# mainv4.net
KiCad netlist of a schematic drawn in EAGLE
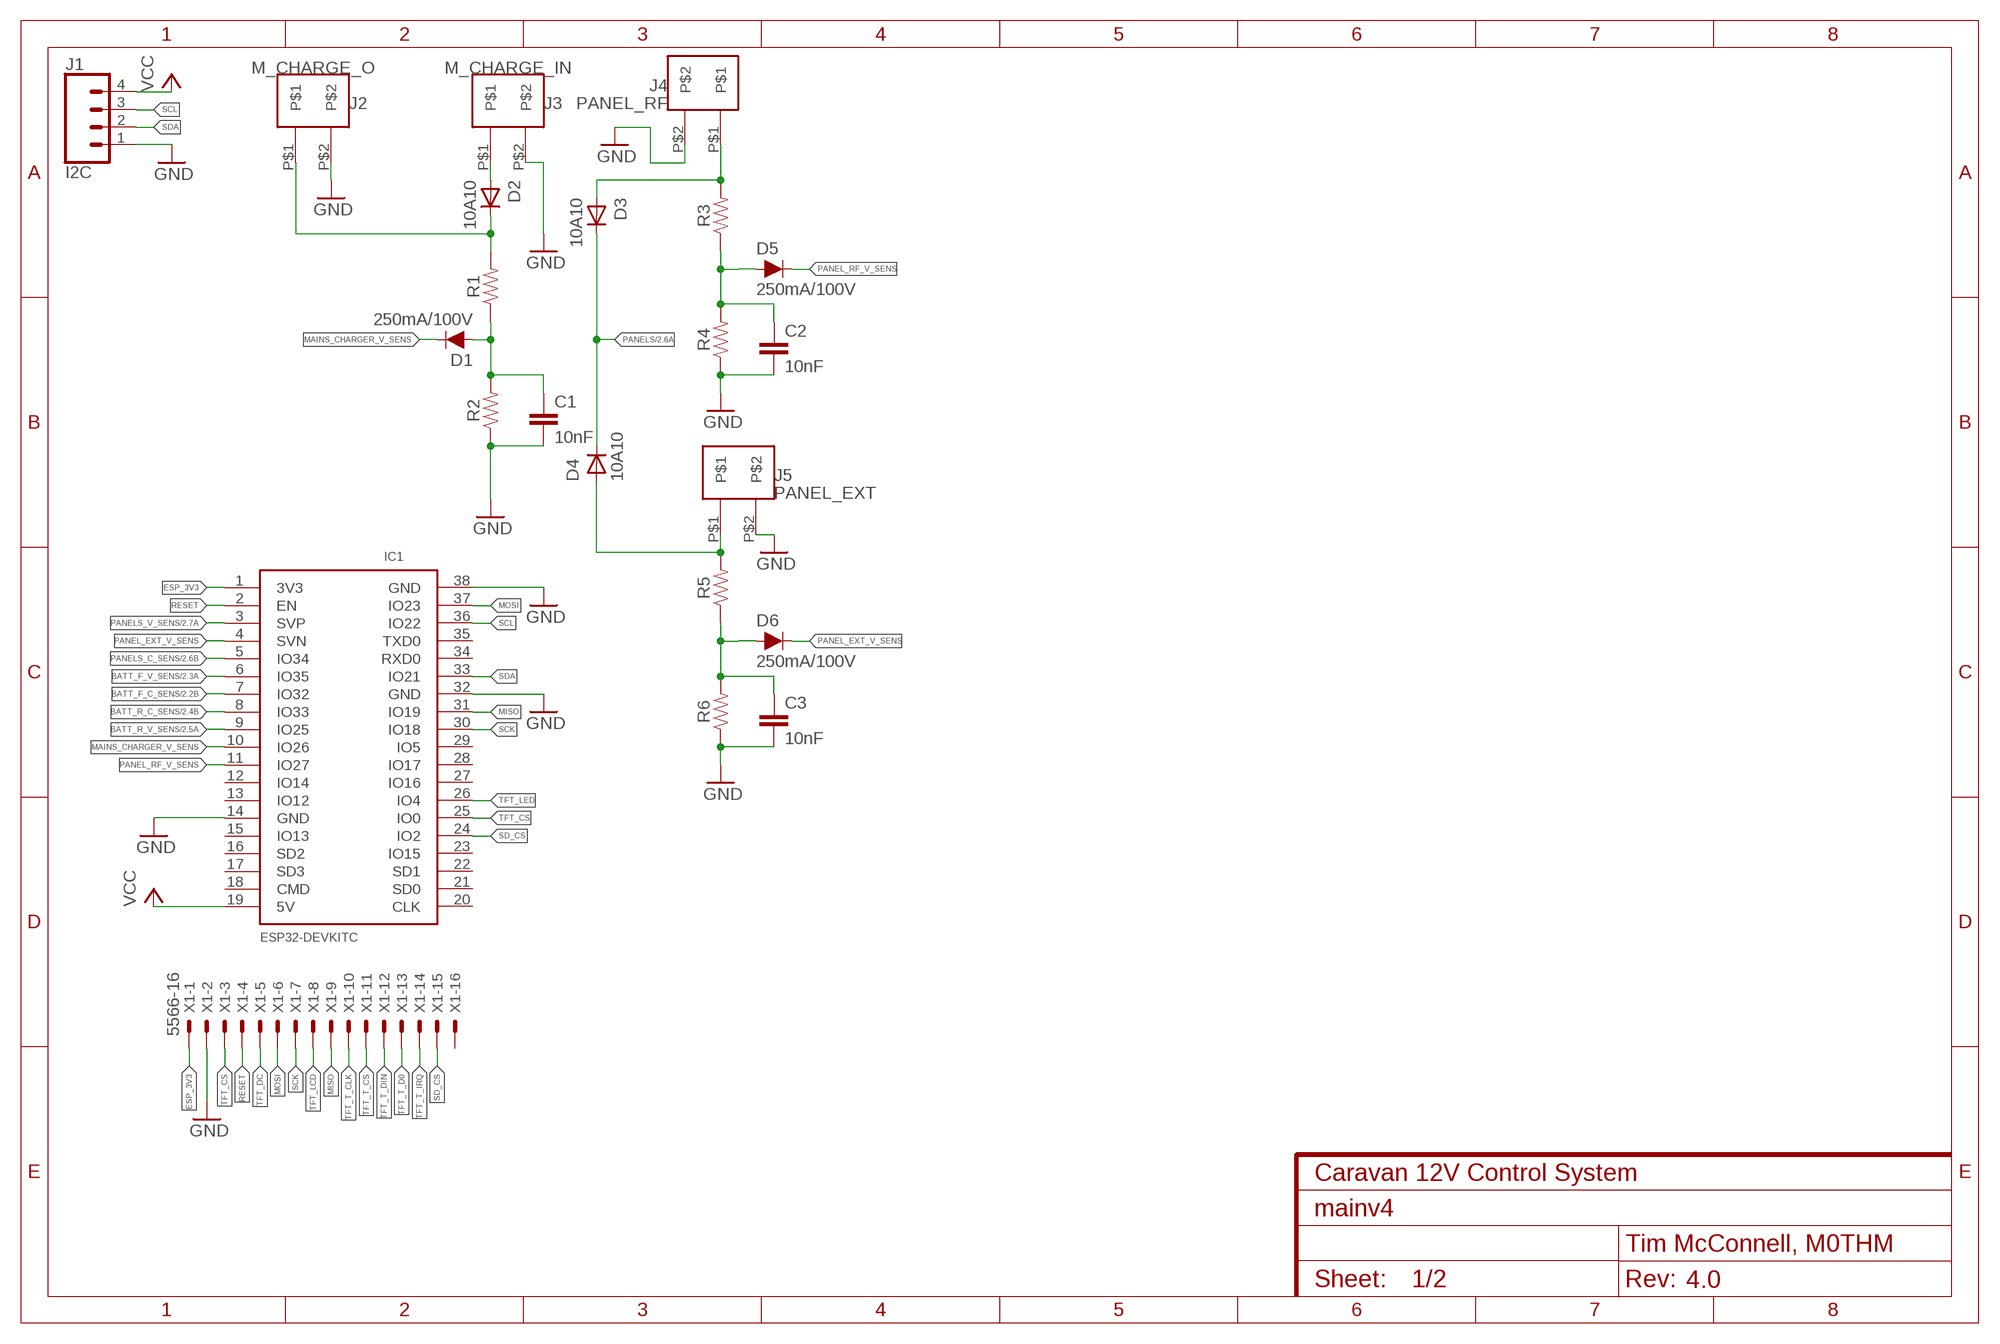
[diagram p0: schematic, sheet 1]
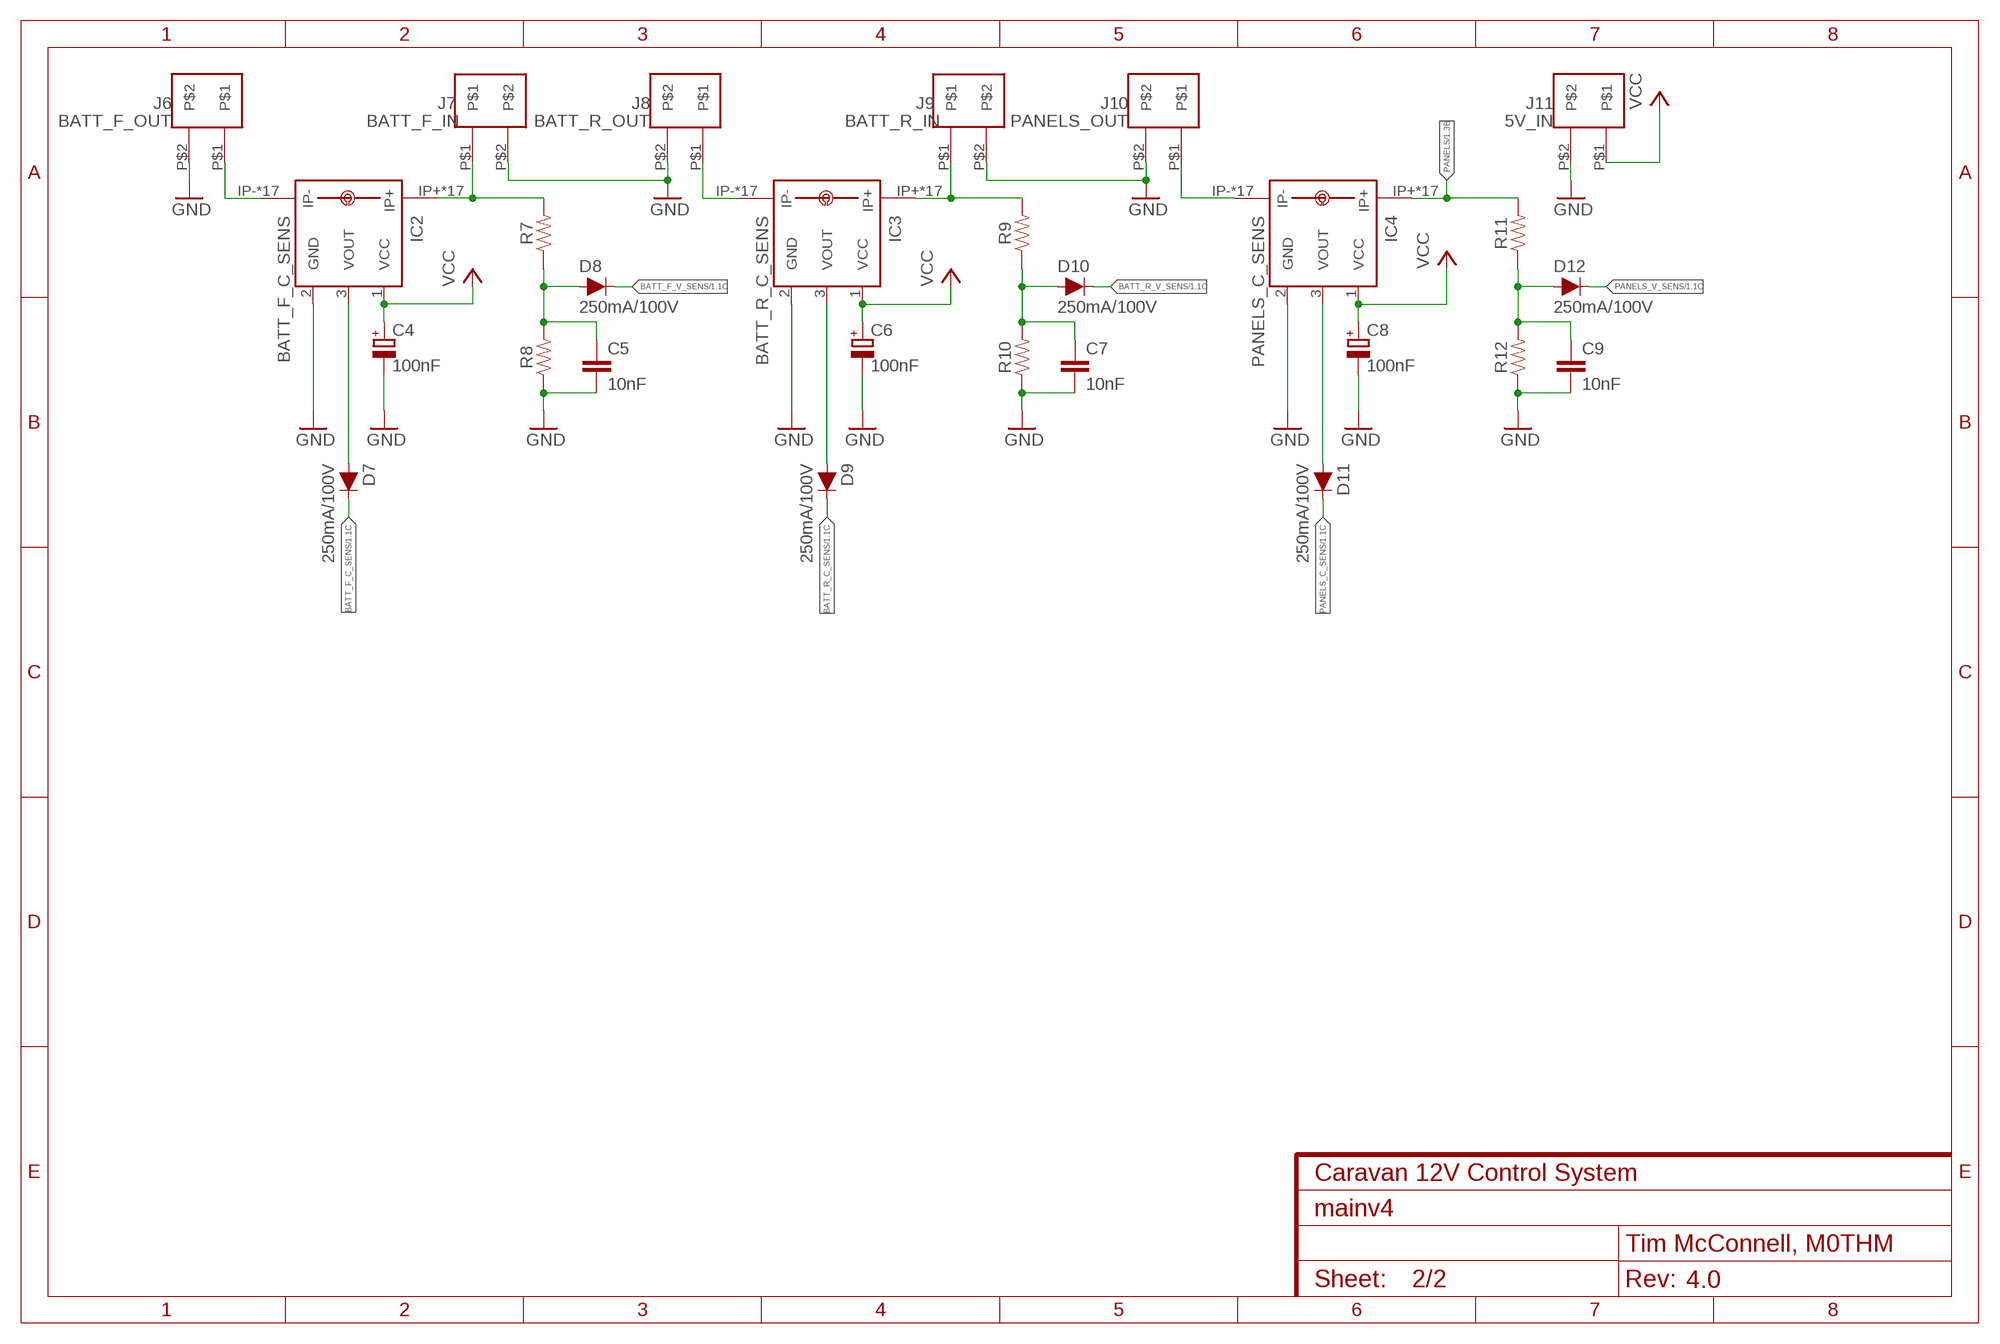
[diagram p1: schematic, sheet 2]

(export (version "E")
  (design (tool "Eeschema 10.0.6"))
  (components
    (comp (ref "C4")
      (value "100nF")
      (footprint "eagle-import:PANASONIC_E")
      (libsource (lib "eagle-import") (part "CPOL-EUE"))
    )
    (comp (ref "C5")
      (value "10nF")
      (footprint "eagle-import:0603")
      (libsource (lib "eagle-import") (part "10NF-0603-50V-10%"))
    )
    (comp (ref "C6")
      (value "100nF")
      (footprint "eagle-import:PANASONIC_E")
      (libsource (lib "eagle-import") (part "CPOL-EUE"))
    )
    (comp (ref "C7")
      (value "10nF")
      (footprint "eagle-import:0603")
      (libsource (lib "eagle-import") (part "10NF-0603-50V-10%"))
    )
    (comp (ref "C8")
      (value "100nF")
      (footprint "eagle-import:PANASONIC_E")
      (libsource (lib "eagle-import") (part "CPOL-EUE"))
    )
    (comp (ref "C9")
      (value "10nF")
      (footprint "eagle-import:0603")
      (libsource (lib "eagle-import") (part "10NF-0603-50V-10%"))
    )
    (comp (ref "D7")
      (value "250mA/100V")
      (footprint "eagle-import:SOD-323")
      (libsource (lib "eagle-import") (part "DIODE-BAS16J"))
    )
    (comp (ref "D8")
      (value "250mA/100V")
      (footprint "eagle-import:SOD-323")
      (libsource (lib "eagle-import") (part "DIODE-BAS16J"))
    )
    (comp (ref "D9")
      (value "250mA/100V")
      (footprint "eagle-import:SOD-323")
      (libsource (lib "eagle-import") (part "DIODE-BAS16J"))
    )
    (comp (ref "D10")
      (value "250mA/100V")
      (footprint "eagle-import:SOD-323")
      (libsource (lib "eagle-import") (part "DIODE-BAS16J"))
    )
    (comp (ref "D11")
      (value "250mA/100V")
      (footprint "eagle-import:SOD-323")
      (libsource (lib "eagle-import") (part "DIODE-BAS16J"))
    )
    (comp (ref "D12")
      (value "250mA/100V")
      (footprint "eagle-import:SOD-323")
      (libsource (lib "eagle-import") (part "DIODE-BAS16J"))
    )
    (comp (ref "IC2")
      (value "BATT_F_C_SENS")
      (footprint "eagle-import:CB-PFF")
      (fields (field (name "MPN") "ACS758ECB-200B-PFF-T"))
      (libsource (lib "eagle-import") (part "ACS758ECB-200B-PFF-T"))
    )
    (comp (ref "IC3")
      (value "BATT_R_C_SENS")
      (footprint "eagle-import:CB-PFF")
      (fields (field (name "MPN") "ACS758ECB-200B-PFF-T"))
      (libsource (lib "eagle-import") (part "ACS758ECB-200B-PFF-T"))
    )
    (comp (ref "IC4")
      (value "PANELS_C_SENS")
      (footprint "eagle-import:CB-PFF")
      (fields (field (name "MPN") "ACS758ECB-200B-PFF-T"))
      (libsource (lib "eagle-import") (part "ACS758ECB-200B-PFF-T"))
    )
    (comp (ref "J6")
      (value "BATT_F_OUT")
      (footprint "eagle-import:40A-2PIN")
      (libsource (lib "eagle-import") (part "40A-2PIN"))
    )
    (comp (ref "J7")
      (value "BATT_F_IN")
      (footprint "eagle-import:40A-2PIN")
      (libsource (lib "eagle-import") (part "40A-2PIN"))
    )
    (comp (ref "J8")
      (value "BATT_R_OUT")
      (footprint "eagle-import:40A-2PIN")
      (libsource (lib "eagle-import") (part "40A-2PIN"))
    )
    (comp (ref "J9")
      (value "BATT_R_IN")
      (footprint "eagle-import:40A-2PIN")
      (libsource (lib "eagle-import") (part "40A-2PIN"))
    )
    (comp (ref "J10")
      (value "PANELS_OUT")
      (footprint "eagle-import:40A-2PIN")
      (libsource (lib "eagle-import") (part "40A-2PIN"))
    )
    (comp (ref "J11")
      (value "5V_IN")
      (footprint "eagle-import:40A-2PIN")
      (libsource (lib "eagle-import") (part "40A-2PIN"))
    )
    (comp (ref "R7")
      (value "RESISTOR0805")
      (footprint "eagle-import:0805")
      (libsource (lib "eagle-import") (part "RESISTOR0805"))
    )
    (comp (ref "R8")
      (value "RESISTOR0805")
      (footprint "eagle-import:0805")
      (libsource (lib "eagle-import") (part "RESISTOR0805"))
    )
    (comp (ref "R9")
      (value "RESISTOR0805")
      (footprint "eagle-import:0805")
      (libsource (lib "eagle-import") (part "RESISTOR0805"))
    )
    (comp (ref "R10")
      (value "RESISTOR0805")
      (footprint "eagle-import:0805")
      (libsource (lib "eagle-import") (part "RESISTOR0805"))
    )
    (comp (ref "R11")
      (value "RESISTOR0805")
      (footprint "eagle-import:0805")
      (libsource (lib "eagle-import") (part "RESISTOR0805"))
    )
    (comp (ref "R12")
      (value "RESISTOR0805")
      (footprint "eagle-import:0805")
      (libsource (lib "eagle-import") (part "RESISTOR0805"))
    )
    (comp (ref "C1")
      (value "10nF")
      (footprint "eagle-import:0603")
      (libsource (lib "eagle-import") (part "10NF-0603-50V-10%"))
    )
    (comp (ref "C2")
      (value "10nF")
      (footprint "eagle-import:0603")
      (libsource (lib "eagle-import") (part "10NF-0603-50V-10%"))
    )
    (comp (ref "C3")
      (value "10nF")
      (footprint "eagle-import:0603")
      (libsource (lib "eagle-import") (part "10NF-0603-50V-10%"))
    )
    (comp (ref "D1")
      (value "250mA/100V")
      (footprint "eagle-import:SOD-323")
      (libsource (lib "eagle-import") (part "DIODE-BAS16J"))
    )
    (comp (ref "D2")
      (value "10A10")
      (footprint "eagle-import:AG")
      (libsource (lib "eagle-import") (part "10A10"))
    )
    (comp (ref "D3")
      (value "10A10")
      (footprint "eagle-import:AG")
      (libsource (lib "eagle-import") (part "10A10"))
    )
    (comp (ref "D4")
      (value "10A10")
      (footprint "eagle-import:AG")
      (libsource (lib "eagle-import") (part "10A10"))
    )
    (comp (ref "D5")
      (value "250mA/100V")
      (footprint "eagle-import:SOD-323")
      (libsource (lib "eagle-import") (part "DIODE-BAS16J"))
    )
    (comp (ref "D6")
      (value "250mA/100V")
      (footprint "eagle-import:SOD-323")
      (libsource (lib "eagle-import") (part "DIODE-BAS16J"))
    )
    (comp (ref "IC1")
      (value "ESP32DEVKITC")
      (footprint "eagle-import:ESP32-DEVKITC")
      (libsource (lib "eagle-import") (part "ESP32DEVKITC"))
    )
    (comp (ref "J1")
      (value "I2C")
      (footprint "eagle-import:MOLEX-1X4")
      (libsource (lib "eagle-import") (part "CONN_04POLAR"))
    )
    (comp (ref "J2")
      (value "M_CHARGE_O")
      (footprint "eagle-import:40A-2PIN")
      (libsource (lib "eagle-import") (part "40A-2PIN"))
    )
    (comp (ref "J3")
      (value "M_CHARGE_IN")
      (footprint "eagle-import:40A-2PIN")
      (libsource (lib "eagle-import") (part "40A-2PIN"))
    )
    (comp (ref "J4")
      (value "PANEL_RF")
      (footprint "eagle-import:40A-2PIN")
      (libsource (lib "eagle-import") (part "40A-2PIN"))
    )
    (comp (ref "J5")
      (value "PANEL_EXT")
      (footprint "eagle-import:40A-2PIN")
      (libsource (lib "eagle-import") (part "40A-2PIN"))
    )
    (comp (ref "R1")
      (value "RESISTOR0805")
      (footprint "eagle-import:0805")
      (libsource (lib "eagle-import") (part "RESISTOR0805"))
    )
    (comp (ref "R2")
      (value "RESISTOR0805")
      (footprint "eagle-import:0805")
      (libsource (lib "eagle-import") (part "RESISTOR0805"))
    )
    (comp (ref "R3")
      (value "RESISTOR0805")
      (footprint "eagle-import:0805")
      (libsource (lib "eagle-import") (part "RESISTOR0805"))
    )
    (comp (ref "R4")
      (value "RESISTOR0805")
      (footprint "eagle-import:0805")
      (libsource (lib "eagle-import") (part "RESISTOR0805"))
    )
    (comp (ref "R5")
      (value "RESISTOR0805")
      (footprint "eagle-import:0805")
      (libsource (lib "eagle-import") (part "RESISTOR0805"))
    )
    (comp (ref "R6")
      (value "RESISTOR0805")
      (footprint "eagle-import:0805")
      (libsource (lib "eagle-import") (part "RESISTOR0805"))
    )
    (comp (ref "X1")
      (value "5566-16")
      (footprint "eagle-import:5566-16")
      (fields (field (name "MF") "MOLEX"))
      (libsource (lib "eagle-import") (part "5566-16"))
    )
  )
  (nets
    (net (code "1") (name "BATT_F_C_SENS") (class "Default")
      (node (ref "D7") (pin "C") (pinfunction "C_C") (pintype "passive"))
      (node (ref "IC1") (pin "7") (pinfunction "IO32_7") (pintype "bidirectional"))
    )
    (net (code "2") (name "BATT_F_V_SENS") (class "Default")
      (node (ref "D8") (pin "C") (pinfunction "C_C") (pintype "passive"))
      (node (ref "IC1") (pin "6") (pinfunction "IO35_6") (pintype "bidirectional"))
    )
    (net (code "3") (name "BATT_R_C_SENS") (class "Default")
      (node (ref "D9") (pin "C") (pinfunction "C_C") (pintype "passive"))
      (node (ref "IC1") (pin "8") (pinfunction "IO33_8") (pintype "bidirectional"))
    )
    (net (code "4") (name "BATT_R_V_SENS") (class "Default")
      (node (ref "D10") (pin "C") (pinfunction "C_C") (pintype "passive"))
      (node (ref "IC1") (pin "9") (pinfunction "IO25_9") (pintype "bidirectional"))
    )
    (net (code "5") (name "ESP_3V3") (class "Default")
      (node (ref "IC1") (pin "1") (pinfunction "3V3_1") (pintype "bidirectional"))
      (node (ref "X1") (pin "1") (pinfunction "S_1") (pintype "passive"))
    )
    (net (code "6") (name "GND") (class "Default")
      (node (ref "C1") (pin "2") (pinfunction "2_2") (pintype "passive"))
      (node (ref "C2") (pin "2") (pinfunction "2_2") (pintype "passive"))
      (node (ref "C3") (pin "2") (pinfunction "2_2") (pintype "passive"))
      (node (ref "C4") (pin "-") (pinfunction "-_-") (pintype "passive"))
      (node (ref "C5") (pin "2") (pinfunction "2_2") (pintype "passive"))
      (node (ref "C6") (pin "-") (pinfunction "-_-") (pintype "passive"))
      (node (ref "C7") (pin "2") (pinfunction "2_2") (pintype "passive"))
      (node (ref "C8") (pin "-") (pinfunction "-_-") (pintype "passive"))
      (node (ref "C9") (pin "2") (pinfunction "2_2") (pintype "passive"))
      (node (ref "IC1") (pin "14") (pinfunction "GND_14") (pintype "bidirectional"))
      (node (ref "IC1") (pin "32") (pinfunction "GND_32") (pintype "bidirectional"))
      (node (ref "IC1") (pin "38") (pinfunction "GND_38") (pintype "bidirectional"))
      (node (ref "IC2") (pin "2") (pinfunction "GND_2") (pintype "power_in"))
      (node (ref "IC3") (pin "2") (pinfunction "GND_2") (pintype "power_in"))
      (node (ref "IC4") (pin "2") (pinfunction "GND_2") (pintype "power_in"))
      (node (ref "J1") (pin "1") (pinfunction "1_1") (pintype "passive"))
      (node (ref "J10") (pin "P$2") (pinfunction "P$2_P$2") (pintype "bidirectional"))
      (node (ref "J11") (pin "P$2") (pinfunction "P$2_P$2") (pintype "bidirectional"))
      (node (ref "J2") (pin "P$2") (pinfunction "P$2_P$2") (pintype "bidirectional"))
      (node (ref "J3") (pin "P$2") (pinfunction "P$2_P$2") (pintype "bidirectional"))
      (node (ref "J4") (pin "P$2") (pinfunction "P$2_P$2") (pintype "bidirectional"))
      (node (ref "J5") (pin "P$2") (pinfunction "P$2_P$2") (pintype "bidirectional"))
      (node (ref "J6") (pin "P$2") (pinfunction "P$2_P$2") (pintype "bidirectional"))
      (node (ref "J7") (pin "P$2") (pinfunction "P$2_P$2") (pintype "bidirectional"))
      (node (ref "J8") (pin "P$2") (pinfunction "P$2_P$2") (pintype "bidirectional"))
      (node (ref "J9") (pin "P$2") (pinfunction "P$2_P$2") (pintype "bidirectional"))
      (node (ref "R10") (pin "1") (pinfunction "1_1") (pintype "passive"))
      (node (ref "R12") (pin "1") (pinfunction "1_1") (pintype "passive"))
      (node (ref "R2") (pin "1") (pinfunction "1_1") (pintype "passive"))
      (node (ref "R4") (pin "1") (pinfunction "1_1") (pintype "passive"))
      (node (ref "R6") (pin "1") (pinfunction "1_1") (pintype "passive"))
      (node (ref "R8") (pin "1") (pinfunction "1_1") (pintype "passive"))
      (node (ref "X1") (pin "2") (pinfunction "S_2") (pintype "passive"))
    )
    (net (code "7") (name "MAINS_CHARGER_V_SENS") (class "Default")
      (node (ref "D1") (pin "C") (pinfunction "C_C") (pintype "passive"))
      (node (ref "IC1") (pin "10") (pinfunction "IO26_10") (pintype "bidirectional"))
    )
    (net (code "8") (name "MISO") (class "Default")
      (node (ref "IC1") (pin "31") (pinfunction "IO19_31") (pintype "bidirectional"))
      (node (ref "X1") (pin "9") (pinfunction "S_9") (pintype "passive"))
    )
    (net (code "9") (name "MOSI") (class "Default")
      (node (ref "IC1") (pin "37") (pinfunction "IO23_37") (pintype "bidirectional"))
      (node (ref "X1") (pin "6") (pinfunction "S_6") (pintype "passive"))
    )
    (net (code "10") (name "Net-(C1-Pad1)") (class "Default")
      (node (ref "C1") (pin "1") (pinfunction "1_1") (pintype "passive"))
      (node (ref "D1") (pin "A") (pinfunction "A_A") (pintype "passive"))
      (node (ref "R1") (pin "1") (pinfunction "1_1") (pintype "passive"))
      (node (ref "R2") (pin "2") (pinfunction "2_2") (pintype "passive"))
    )
    (net (code "11") (name "Net-(C2-Pad1)") (class "Default")
      (node (ref "C2") (pin "1") (pinfunction "1_1") (pintype "passive"))
      (node (ref "D5") (pin "A") (pinfunction "A_A") (pintype "passive"))
      (node (ref "R3") (pin "1") (pinfunction "1_1") (pintype "passive"))
      (node (ref "R4") (pin "2") (pinfunction "2_2") (pintype "passive"))
    )
    (net (code "12") (name "Net-(C3-Pad1)") (class "Default")
      (node (ref "C3") (pin "1") (pinfunction "1_1") (pintype "passive"))
      (node (ref "D6") (pin "A") (pinfunction "A_A") (pintype "passive"))
      (node (ref "R5") (pin "1") (pinfunction "1_1") (pintype "passive"))
      (node (ref "R6") (pin "2") (pinfunction "2_2") (pintype "passive"))
    )
    (net (code "13") (name "Net-(C5-Pad1)") (class "Default")
      (node (ref "C5") (pin "1") (pinfunction "1_1") (pintype "passive"))
      (node (ref "D8") (pin "A") (pinfunction "A_A") (pintype "passive"))
      (node (ref "R7") (pin "1") (pinfunction "1_1") (pintype "passive"))
      (node (ref "R8") (pin "2") (pinfunction "2_2") (pintype "passive"))
    )
    (net (code "14") (name "Net-(C7-Pad1)") (class "Default")
      (node (ref "C7") (pin "1") (pinfunction "1_1") (pintype "passive"))
      (node (ref "D10") (pin "A") (pinfunction "A_A") (pintype "passive"))
      (node (ref "R10") (pin "2") (pinfunction "2_2") (pintype "passive"))
      (node (ref "R9") (pin "1") (pinfunction "1_1") (pintype "passive"))
    )
    (net (code "15") (name "Net-(C9-Pad1)") (class "Default")
      (node (ref "C9") (pin "1") (pinfunction "1_1") (pintype "passive"))
      (node (ref "D12") (pin "A") (pinfunction "A_A") (pintype "passive"))
      (node (ref "R11") (pin "1") (pinfunction "1_1") (pintype "passive"))
      (node (ref "R12") (pin "2") (pinfunction "2_2") (pintype "passive"))
    )
    (net (code "16") (name "Net-(D2-PadA)") (class "Default")
      (node (ref "D2") (pin "A") (pinfunction "A_A") (pintype "passive"))
      (node (ref "J3") (pin "P$1") (pinfunction "P$1_P$1") (pintype "bidirectional"))
    )
    (net (code "17") (name "Net-(D2-PadC)") (class "Default")
      (node (ref "D2") (pin "C") (pinfunction "C_C") (pintype "passive"))
      (node (ref "J2") (pin "P$1") (pinfunction "P$1_P$1") (pintype "bidirectional"))
      (node (ref "R1") (pin "2") (pinfunction "2_2") (pintype "passive"))
    )
    (net (code "18") (name "Net-(D3-PadA)") (class "Default")
      (node (ref "D3") (pin "A") (pinfunction "A_A") (pintype "passive"))
      (node (ref "J4") (pin "P$1") (pinfunction "P$1_P$1") (pintype "bidirectional"))
      (node (ref "R3") (pin "2") (pinfunction "2_2") (pintype "passive"))
    )
    (net (code "19") (name "Net-(D4-PadA)") (class "Default")
      (node (ref "D4") (pin "A") (pinfunction "A_A") (pintype "passive"))
      (node (ref "J5") (pin "P$1") (pinfunction "P$1_P$1") (pintype "bidirectional"))
      (node (ref "R5") (pin "2") (pinfunction "2_2") (pintype "passive"))
    )
    (net (code "20") (name "Net-(IC2-IP+-PadIP+@10)") (class "Default")
      (node (ref "IC2") (pin "IP+") (pinfunction "IP+_IP+") (pintype "passive"))
      (node (ref "IC2") (pin "IP+@10") (pinfunction "IP+_IP+@10") (pintype "passive"))
      (node (ref "IC2") (pin "IP+@11") (pinfunction "IP+_IP+@11") (pintype "passive"))
      (node (ref "IC2") (pin "IP+@12") (pinfunction "IP+_IP+@12") (pintype "passive"))
      (node (ref "IC2") (pin "IP+@13") (pinfunction "IP+_IP+@13") (pintype "passive"))
      (node (ref "IC2") (pin "IP+@14") (pinfunction "IP+_IP+@14") (pintype "passive"))
      (node (ref "IC2") (pin "IP+@15") (pinfunction "IP+_IP+@15") (pintype "passive"))
      (node (ref "IC2") (pin "IP+@16") (pinfunction "IP+_IP+@16") (pintype "passive"))
      (node (ref "IC2") (pin "IP+@17") (pinfunction "IP+_IP+@17") (pintype "passive"))
      (node (ref "IC2") (pin "IP+@2") (pinfunction "IP+_IP+@2") (pintype "passive"))
      (node (ref "IC2") (pin "IP+@3") (pinfunction "IP+_IP+@3") (pintype "passive"))
      (node (ref "IC2") (pin "IP+@4") (pinfunction "IP+_IP+@4") (pintype "passive"))
      (node (ref "IC2") (pin "IP+@5") (pinfunction "IP+_IP+@5") (pintype "passive"))
      (node (ref "IC2") (pin "IP+@6") (pinfunction "IP+_IP+@6") (pintype "passive"))
      (node (ref "IC2") (pin "IP+@7") (pinfunction "IP+_IP+@7") (pintype "passive"))
      (node (ref "IC2") (pin "IP+@8") (pinfunction "IP+_IP+@8") (pintype "passive"))
      (node (ref "IC2") (pin "IP+@9") (pinfunction "IP+_IP+@9") (pintype "passive"))
      (node (ref "J7") (pin "P$1") (pinfunction "P$1_P$1") (pintype "bidirectional"))
      (node (ref "R7") (pin "2") (pinfunction "2_2") (pintype "passive"))
    )
    (net (code "21") (name "Net-(IC2-IP--PadIP-@10)") (class "Default")
      (node (ref "IC2") (pin "IP-") (pinfunction "IP-_IP-") (pintype "passive"))
      (node (ref "IC2") (pin "IP-@10") (pinfunction "IP-_IP-@10") (pintype "passive"))
      (node (ref "IC2") (pin "IP-@11") (pinfunction "IP-_IP-@11") (pintype "passive"))
      (node (ref "IC2") (pin "IP-@12") (pinfunction "IP-_IP-@12") (pintype "passive"))
      (node (ref "IC2") (pin "IP-@13") (pinfunction "IP-_IP-@13") (pintype "passive"))
      (node (ref "IC2") (pin "IP-@14") (pinfunction "IP-_IP-@14") (pintype "passive"))
      (node (ref "IC2") (pin "IP-@15") (pinfunction "IP-_IP-@15") (pintype "passive"))
      (node (ref "IC2") (pin "IP-@16") (pinfunction "IP-_IP-@16") (pintype "passive"))
      (node (ref "IC2") (pin "IP-@17") (pinfunction "IP-_IP-@17") (pintype "passive"))
      (node (ref "IC2") (pin "IP-@2") (pinfunction "IP-_IP-@2") (pintype "passive"))
      (node (ref "IC2") (pin "IP-@3") (pinfunction "IP-_IP-@3") (pintype "passive"))
      (node (ref "IC2") (pin "IP-@4") (pinfunction "IP-_IP-@4") (pintype "passive"))
      (node (ref "IC2") (pin "IP-@5") (pinfunction "IP-_IP-@5") (pintype "passive"))
      (node (ref "IC2") (pin "IP-@6") (pinfunction "IP-_IP-@6") (pintype "passive"))
      (node (ref "IC2") (pin "IP-@7") (pinfunction "IP-_IP-@7") (pintype "passive"))
      (node (ref "IC2") (pin "IP-@8") (pinfunction "IP-_IP-@8") (pintype "passive"))
      (node (ref "IC2") (pin "IP-@9") (pinfunction "IP-_IP-@9") (pintype "passive"))
      (node (ref "J6") (pin "P$1") (pinfunction "P$1_P$1") (pintype "bidirectional"))
    )
    (net (code "22") (name "Net-(IC2-VOUT)") (class "Default")
      (node (ref "D7") (pin "A") (pinfunction "A_A") (pintype "passive"))
      (node (ref "IC2") (pin "3") (pinfunction "VOUT_3") (pintype "output"))
    )
    (net (code "23") (name "Net-(IC3-IP+-PadIP+@10)") (class "Default")
      (node (ref "IC3") (pin "IP+") (pinfunction "IP+_IP+") (pintype "passive"))
      (node (ref "IC3") (pin "IP+@10") (pinfunction "IP+_IP+@10") (pintype "passive"))
      (node (ref "IC3") (pin "IP+@11") (pinfunction "IP+_IP+@11") (pintype "passive"))
      (node (ref "IC3") (pin "IP+@12") (pinfunction "IP+_IP+@12") (pintype "passive"))
      (node (ref "IC3") (pin "IP+@13") (pinfunction "IP+_IP+@13") (pintype "passive"))
      (node (ref "IC3") (pin "IP+@14") (pinfunction "IP+_IP+@14") (pintype "passive"))
      (node (ref "IC3") (pin "IP+@15") (pinfunction "IP+_IP+@15") (pintype "passive"))
      (node (ref "IC3") (pin "IP+@16") (pinfunction "IP+_IP+@16") (pintype "passive"))
      (node (ref "IC3") (pin "IP+@17") (pinfunction "IP+_IP+@17") (pintype "passive"))
      (node (ref "IC3") (pin "IP+@2") (pinfunction "IP+_IP+@2") (pintype "passive"))
      (node (ref "IC3") (pin "IP+@3") (pinfunction "IP+_IP+@3") (pintype "passive"))
      (node (ref "IC3") (pin "IP+@4") (pinfunction "IP+_IP+@4") (pintype "passive"))
      (node (ref "IC3") (pin "IP+@5") (pinfunction "IP+_IP+@5") (pintype "passive"))
      (node (ref "IC3") (pin "IP+@6") (pinfunction "IP+_IP+@6") (pintype "passive"))
      (node (ref "IC3") (pin "IP+@7") (pinfunction "IP+_IP+@7") (pintype "passive"))
      (node (ref "IC3") (pin "IP+@8") (pinfunction "IP+_IP+@8") (pintype "passive"))
      (node (ref "IC3") (pin "IP+@9") (pinfunction "IP+_IP+@9") (pintype "passive"))
      (node (ref "J9") (pin "P$1") (pinfunction "P$1_P$1") (pintype "bidirectional"))
      (node (ref "R9") (pin "2") (pinfunction "2_2") (pintype "passive"))
    )
    (net (code "24") (name "Net-(IC3-IP--PadIP-@10)") (class "Default")
      (node (ref "IC3") (pin "IP-") (pinfunction "IP-_IP-") (pintype "passive"))
      (node (ref "IC3") (pin "IP-@10") (pinfunction "IP-_IP-@10") (pintype "passive"))
      (node (ref "IC3") (pin "IP-@11") (pinfunction "IP-_IP-@11") (pintype "passive"))
      (node (ref "IC3") (pin "IP-@12") (pinfunction "IP-_IP-@12") (pintype "passive"))
      (node (ref "IC3") (pin "IP-@13") (pinfunction "IP-_IP-@13") (pintype "passive"))
      (node (ref "IC3") (pin "IP-@14") (pinfunction "IP-_IP-@14") (pintype "passive"))
      (node (ref "IC3") (pin "IP-@15") (pinfunction "IP-_IP-@15") (pintype "passive"))
      (node (ref "IC3") (pin "IP-@16") (pinfunction "IP-_IP-@16") (pintype "passive"))
      (node (ref "IC3") (pin "IP-@17") (pinfunction "IP-_IP-@17") (pintype "passive"))
      (node (ref "IC3") (pin "IP-@2") (pinfunction "IP-_IP-@2") (pintype "passive"))
      (node (ref "IC3") (pin "IP-@3") (pinfunction "IP-_IP-@3") (pintype "passive"))
      (node (ref "IC3") (pin "IP-@4") (pinfunction "IP-_IP-@4") (pintype "passive"))
      (node (ref "IC3") (pin "IP-@5") (pinfunction "IP-_IP-@5") (pintype "passive"))
      (node (ref "IC3") (pin "IP-@6") (pinfunction "IP-_IP-@6") (pintype "passive"))
      (node (ref "IC3") (pin "IP-@7") (pinfunction "IP-_IP-@7") (pintype "passive"))
      (node (ref "IC3") (pin "IP-@8") (pinfunction "IP-_IP-@8") (pintype "passive"))
      (node (ref "IC3") (pin "IP-@9") (pinfunction "IP-_IP-@9") (pintype "passive"))
      (node (ref "J8") (pin "P$1") (pinfunction "P$1_P$1") (pintype "bidirectional"))
    )
    (net (code "25") (name "Net-(IC3-VOUT)") (class "Default")
      (node (ref "D9") (pin "A") (pinfunction "A_A") (pintype "passive"))
      (node (ref "IC3") (pin "3") (pinfunction "VOUT_3") (pintype "output"))
    )
    (net (code "26") (name "Net-(IC4-IP--PadIP-@10)") (class "Default")
      (node (ref "IC4") (pin "IP-") (pinfunction "IP-_IP-") (pintype "passive"))
      (node (ref "IC4") (pin "IP-@10") (pinfunction "IP-_IP-@10") (pintype "passive"))
      (node (ref "IC4") (pin "IP-@11") (pinfunction "IP-_IP-@11") (pintype "passive"))
      (node (ref "IC4") (pin "IP-@12") (pinfunction "IP-_IP-@12") (pintype "passive"))
      (node (ref "IC4") (pin "IP-@13") (pinfunction "IP-_IP-@13") (pintype "passive"))
      (node (ref "IC4") (pin "IP-@14") (pinfunction "IP-_IP-@14") (pintype "passive"))
      (node (ref "IC4") (pin "IP-@15") (pinfunction "IP-_IP-@15") (pintype "passive"))
      (node (ref "IC4") (pin "IP-@16") (pinfunction "IP-_IP-@16") (pintype "passive"))
      (node (ref "IC4") (pin "IP-@17") (pinfunction "IP-_IP-@17") (pintype "passive"))
      (node (ref "IC4") (pin "IP-@2") (pinfunction "IP-_IP-@2") (pintype "passive"))
      (node (ref "IC4") (pin "IP-@3") (pinfunction "IP-_IP-@3") (pintype "passive"))
      (node (ref "IC4") (pin "IP-@4") (pinfunction "IP-_IP-@4") (pintype "passive"))
      (node (ref "IC4") (pin "IP-@5") (pinfunction "IP-_IP-@5") (pintype "passive"))
      (node (ref "IC4") (pin "IP-@6") (pinfunction "IP-_IP-@6") (pintype "passive"))
      (node (ref "IC4") (pin "IP-@7") (pinfunction "IP-_IP-@7") (pintype "passive"))
      (node (ref "IC4") (pin "IP-@8") (pinfunction "IP-_IP-@8") (pintype "passive"))
      (node (ref "IC4") (pin "IP-@9") (pinfunction "IP-_IP-@9") (pintype "passive"))
      (node (ref "J10") (pin "P$1") (pinfunction "P$1_P$1") (pintype "bidirectional"))
    )
    (net (code "27") (name "Net-(IC4-VOUT)") (class "Default")
      (node (ref "D11") (pin "A") (pinfunction "A_A") (pintype "passive"))
      (node (ref "IC4") (pin "3") (pinfunction "VOUT_3") (pintype "output"))
    )
    (net (code "28") (name "PANELS") (class "Default")
      (node (ref "D3") (pin "C") (pinfunction "C_C") (pintype "passive"))
      (node (ref "D4") (pin "C") (pinfunction "C_C") (pintype "passive"))
      (node (ref "IC4") (pin "IP+") (pinfunction "IP+_IP+") (pintype "passive"))
      (node (ref "IC4") (pin "IP+@10") (pinfunction "IP+_IP+@10") (pintype "passive"))
      (node (ref "IC4") (pin "IP+@11") (pinfunction "IP+_IP+@11") (pintype "passive"))
      (node (ref "IC4") (pin "IP+@12") (pinfunction "IP+_IP+@12") (pintype "passive"))
      (node (ref "IC4") (pin "IP+@13") (pinfunction "IP+_IP+@13") (pintype "passive"))
      (node (ref "IC4") (pin "IP+@14") (pinfunction "IP+_IP+@14") (pintype "passive"))
      (node (ref "IC4") (pin "IP+@15") (pinfunction "IP+_IP+@15") (pintype "passive"))
      (node (ref "IC4") (pin "IP+@16") (pinfunction "IP+_IP+@16") (pintype "passive"))
      (node (ref "IC4") (pin "IP+@17") (pinfunction "IP+_IP+@17") (pintype "passive"))
      (node (ref "IC4") (pin "IP+@2") (pinfunction "IP+_IP+@2") (pintype "passive"))
      (node (ref "IC4") (pin "IP+@3") (pinfunction "IP+_IP+@3") (pintype "passive"))
      (node (ref "IC4") (pin "IP+@4") (pinfunction "IP+_IP+@4") (pintype "passive"))
      (node (ref "IC4") (pin "IP+@5") (pinfunction "IP+_IP+@5") (pintype "passive"))
      (node (ref "IC4") (pin "IP+@6") (pinfunction "IP+_IP+@6") (pintype "passive"))
      (node (ref "IC4") (pin "IP+@7") (pinfunction "IP+_IP+@7") (pintype "passive"))
      (node (ref "IC4") (pin "IP+@8") (pinfunction "IP+_IP+@8") (pintype "passive"))
      (node (ref "IC4") (pin "IP+@9") (pinfunction "IP+_IP+@9") (pintype "passive"))
      (node (ref "R11") (pin "2") (pinfunction "2_2") (pintype "passive"))
    )
    (net (code "29") (name "PANELS_C_SENS") (class "Default")
      (node (ref "D11") (pin "C") (pinfunction "C_C") (pintype "passive"))
      (node (ref "IC1") (pin "5") (pinfunction "IO34_5") (pintype "bidirectional"))
    )
    (net (code "30") (name "PANELS_V_SENS") (class "Default")
      (node (ref "D12") (pin "C") (pinfunction "C_C") (pintype "passive"))
      (node (ref "IC1") (pin "3") (pinfunction "SVP_3") (pintype "bidirectional"))
    )
    (net (code "31") (name "PANEL_EXT_V_SENS") (class "Default")
      (node (ref "D6") (pin "C") (pinfunction "C_C") (pintype "passive"))
      (node (ref "IC1") (pin "4") (pinfunction "SVN_4") (pintype "bidirectional"))
    )
    (net (code "32") (name "PANEL_RF_V_SENS") (class "Default")
      (node (ref "D5") (pin "C") (pinfunction "C_C") (pintype "passive"))
      (node (ref "IC1") (pin "11") (pinfunction "IO27_11") (pintype "bidirectional"))
    )
    (net (code "33") (name "RESET") (class "Default")
      (node (ref "IC1") (pin "2") (pinfunction "EN_2") (pintype "bidirectional"))
      (node (ref "X1") (pin "4") (pinfunction "S_4") (pintype "passive"))
    )
    (net (code "34") (name "SCK") (class "Default")
      (node (ref "IC1") (pin "30") (pinfunction "IO18_30") (pintype "bidirectional"))
      (node (ref "X1") (pin "7") (pinfunction "S_7") (pintype "passive"))
    )
    (net (code "35") (name "SCL") (class "Default")
      (node (ref "IC1") (pin "36") (pinfunction "IO22_36") (pintype "bidirectional"))
      (node (ref "J1") (pin "3") (pinfunction "3_3") (pintype "passive"))
    )
    (net (code "36") (name "SDA") (class "Default")
      (node (ref "IC1") (pin "33") (pinfunction "IO21_33") (pintype "bidirectional"))
      (node (ref "J1") (pin "2") (pinfunction "2_2") (pintype "passive"))
    )
    (net (code "37") (name "SD_CS") (class "Default")
      (node (ref "IC1") (pin "24") (pinfunction "IO2_24") (pintype "bidirectional"))
      (node (ref "X1") (pin "15") (pinfunction "S_15") (pintype "passive"))
    )
    (net (code "38") (name "TFT_CS") (class "Default")
      (node (ref "IC1") (pin "25") (pinfunction "IO0_25") (pintype "bidirectional"))
      (node (ref "X1") (pin "3") (pinfunction "S_3") (pintype "passive"))
    )
    (net (code "39") (name "TFT_DC") (class "Default")
      (node (ref "X1") (pin "5") (pinfunction "S_5") (pintype "passive"))
    )
    (net (code "40") (name "TFT_LCD") (class "Default")
      (node (ref "X1") (pin "8") (pinfunction "S_8") (pintype "passive"))
    )
    (net (code "41") (name "TFT_LED") (class "Default")
      (node (ref "IC1") (pin "26") (pinfunction "IO4_26") (pintype "bidirectional"))
    )
    (net (code "42") (name "TFT_T_CLK") (class "Default")
      (node (ref "X1") (pin "10") (pinfunction "S_10") (pintype "passive"))
    )
    (net (code "43") (name "TFT_T_CS") (class "Default")
      (node (ref "X1") (pin "11") (pinfunction "S_11") (pintype "passive"))
    )
    (net (code "44") (name "TFT_T_D0") (class "Default")
      (node (ref "X1") (pin "13") (pinfunction "S_13") (pintype "passive"))
    )
    (net (code "45") (name "TFT_T_DIN") (class "Default")
      (node (ref "X1") (pin "12") (pinfunction "S_12") (pintype "passive"))
    )
    (net (code "46") (name "TFT_T_IRQ") (class "Default")
      (node (ref "X1") (pin "14") (pinfunction "S_14") (pintype "passive"))
    )
    (net (code "47") (name "VCC") (class "Default")
      (node (ref "C4") (pin "+") (pinfunction "+_+") (pintype "passive"))
      (node (ref "C6") (pin "+") (pinfunction "+_+") (pintype "passive"))
      (node (ref "C8") (pin "+") (pinfunction "+_+") (pintype "passive"))
      (node (ref "IC1") (pin "19") (pinfunction "5V_19") (pintype "bidirectional"))
      (node (ref "IC2") (pin "1") (pinfunction "VCC_1") (pintype "power_in"))
      (node (ref "IC3") (pin "1") (pinfunction "VCC_1") (pintype "power_in"))
      (node (ref "IC4") (pin "1") (pinfunction "VCC_1") (pintype "power_in"))
      (node (ref "J1") (pin "4") (pinfunction "4_4") (pintype "passive"))
      (node (ref "J11") (pin "P$1") (pinfunction "P$1_P$1") (pintype "bidirectional"))
    )
    (net (code "48") (name "unconnected-(IC1-CLK-Pad20)") (class "Default")
      (node (ref "IC1") (pin "20") (pinfunction "CLK_20") (pintype "bidirectional"))
    )
    (net (code "49") (name "unconnected-(IC1-CMD-Pad18)") (class "Default")
      (node (ref "IC1") (pin "18") (pinfunction "CMD_18") (pintype "bidirectional"))
    )
    (net (code "50") (name "unconnected-(IC1-IO5-Pad29)") (class "Default")
      (node (ref "IC1") (pin "29") (pinfunction "IO5_29") (pintype "bidirectional"))
    )
    (net (code "51") (name "unconnected-(IC1-IO12-Pad13)") (class "Default")
      (node (ref "IC1") (pin "13") (pinfunction "IO12_13") (pintype "bidirectional"))
    )
    (net (code "52") (name "unconnected-(IC1-IO13-Pad15)") (class "Default")
      (node (ref "IC1") (pin "15") (pinfunction "IO13_15") (pintype "bidirectional"))
    )
    (net (code "53") (name "unconnected-(IC1-IO14-Pad12)") (class "Default")
      (node (ref "IC1") (pin "12") (pinfunction "IO14_12") (pintype "bidirectional"))
    )
    (net (code "54") (name "unconnected-(IC1-IO15-Pad23)") (class "Default")
      (node (ref "IC1") (pin "23") (pinfunction "IO15_23") (pintype "bidirectional"))
    )
    (net (code "55") (name "unconnected-(IC1-IO16-Pad27)") (class "Default")
      (node (ref "IC1") (pin "27") (pinfunction "IO16_27") (pintype "bidirectional"))
    )
    (net (code "56") (name "unconnected-(IC1-IO17-Pad28)") (class "Default")
      (node (ref "IC1") (pin "28") (pinfunction "IO17_28") (pintype "bidirectional"))
    )
    (net (code "57") (name "unconnected-(IC1-RXD0-Pad34)") (class "Default")
      (node (ref "IC1") (pin "34") (pinfunction "RXD0_34") (pintype "bidirectional"))
    )
    (net (code "58") (name "unconnected-(IC1-SD0-Pad21)") (class "Default")
      (node (ref "IC1") (pin "21") (pinfunction "SD0_21") (pintype "bidirectional"))
    )
    (net (code "59") (name "unconnected-(IC1-SD1-Pad22)") (class "Default")
      (node (ref "IC1") (pin "22") (pinfunction "SD1_22") (pintype "bidirectional"))
    )
    (net (code "60") (name "unconnected-(IC1-SD2-Pad16)") (class "Default")
      (node (ref "IC1") (pin "16") (pinfunction "SD2_16") (pintype "bidirectional"))
    )
    (net (code "61") (name "unconnected-(IC1-SD3-Pad17)") (class "Default")
      (node (ref "IC1") (pin "17") (pinfunction "SD3_17") (pintype "bidirectional"))
    )
    (net (code "62") (name "unconnected-(IC1-TXD0-Pad35)") (class "Default")
      (node (ref "IC1") (pin "35") (pinfunction "TXD0_35") (pintype "bidirectional"))
    )
    (net (code "63") (name "unconnected-(X1H-S-Pad16)") (class "Default")
      (node (ref "X1") (pin "16") (pinfunction "S_16") (pintype "passive"))
    )
  )
)
